# POWER.net
KiCad netlist of a schematic drawn in Altium Designer
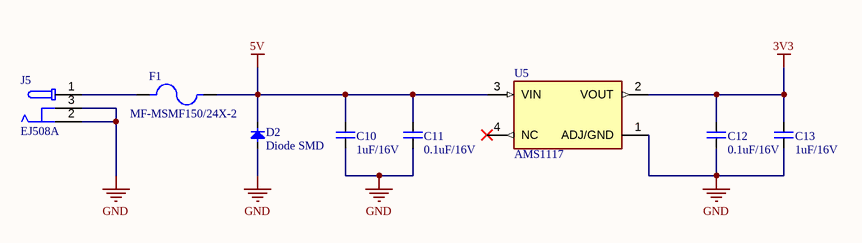
[diagram p0: POWER.SchDoc]

(export (version "E")
  (design (tool "Eeschema 10.0.6"))
  (components
    (comp (ref "C10")
      (value "1uF/16V")
      (footprint "CAP_C_1608X80")
      (description "CAP_Chip")
      (libsource (lib "BTL_SCHLIB") (part "CAP_SMD"))
    )
    (comp (ref "C11")
      (value "0.1uF/16V")
      (footprint "CAP_C_1608X80")
      (description "CAP_Chip")
      (libsource (lib "BTL_SCHLIB") (part "CAP_SMD"))
    )
    (comp (ref "C12")
      (value "0.1uF/16V")
      (footprint "CAP_C_1608X80")
      (description "CAP_Chip")
      (libsource (lib "BTL_SCHLIB") (part "CAP_SMD"))
    )
    (comp (ref "C13")
      (value "1uF/16V")
      (footprint "CAP_C_1608X80")
      (description "CAP_Chip")
      (libsource (lib "BTL_SCHLIB") (part "CAP_SMD"))
    )
    (comp (ref "D2")
      (value "Diode SMD")
      (footprint "DO-214AC_SMA")
      (description "Default Diode")
      (fields (field (name "PUBLISHER") "Altium Limited"))
      (libsource (lib "BTL_SCHLIB") (part "Diode SMD"))
    )
    (comp (ref "F1")
      (value "MF-MSMF150/24X-2")
      (footprint "FUSER_MF-MSMF150/24X-2")
      (description "Polymeric PTC Resettable Fuse 24V 1.5 A Ih Surface Mount 1812 (4532 Metric), Concave")
      (fields (field (name "DIGI-KEY_PART_NUMBER") "MF-MSMF150/24X-2TR-ND") (field (name "MF") "Bourns"))
      (libsource (lib "BTL_SCHLIB") (part "MF-MSMF150/24X-2"))
    )
    (comp (ref "J5")
      (value "EJ508A")
      (footprint "MPD_EJ508A")
      (description "Power Barrel Connector Jack 2.10mm ID _0.083_, 5.50mm OD _0.217_ Through Hole, Right Angle")
      (fields (field (name "MF") "MPD"))
      (libsource (lib "BTL_SCHLIB") (part "EJ508A"))
    )
    (comp (ref "U5")
      (value "AMS1117")
      (footprint "SOT229P700X180-4N")
      (description "1A LOW DROPOUT VOLTAGE REGULATOR SOT-223")
      (fields (field (name "MF") "Advanced Monolithic Systems"))
      (libsource (lib "BTL_SCHLIB") (part "AMS1117"))
    )
  )
  (nets
    (net (code "1") (name "3V3") (class "Default")
      (node (ref "C12") (pin "2") (pinfunction "2_2") (pintype "passive"))
      (node (ref "C13") (pin "2") (pinfunction "2_2") (pintype "passive"))
      (node (ref "U5") (pin "2") (pinfunction "VOUT_2") (pintype "output"))
    )
    (net (code "2") (name "5V") (class "Default")
      (node (ref "C10") (pin "2") (pinfunction "2_2") (pintype "passive"))
      (node (ref "C11") (pin "2") (pinfunction "2_2") (pintype "passive"))
      (node (ref "D2") (pin "1") (pinfunction "K_1") (pintype "passive"))
      (node (ref "F1") (pin "2") (pinfunction "2_2") (pintype "passive"))
      (node (ref "U5") (pin "3") (pinfunction "VIN_3") (pintype "input"))
    )
    (net (code "3") (name "GND") (class "Default")
      (node (ref "C10") (pin "1") (pinfunction "1_1") (pintype "passive"))
      (node (ref "C11") (pin "1") (pinfunction "1_1") (pintype "passive"))
      (node (ref "C12") (pin "1") (pinfunction "1_1") (pintype "passive"))
      (node (ref "C13") (pin "1") (pinfunction "1_1") (pintype "passive"))
      (node (ref "D2") (pin "2") (pinfunction "A_2") (pintype "passive"))
      (node (ref "J5") (pin "2") (pinfunction "2_2") (pintype "passive"))
      (node (ref "J5") (pin "3") (pinfunction "3_3") (pintype "passive"))
      (node (ref "U5") (pin "1") (pinfunction "ADJ/GND_1") (pintype "power_in"))
    )
    (net (code "4") (name "Net-(F1-Pad1)") (class "Default")
      (node (ref "F1") (pin "1") (pinfunction "1_1") (pintype "passive"))
      (node (ref "J5") (pin "1") (pinfunction "1_1") (pintype "passive"))
    )
    (net (code "5") (name "unconnected-(U5-NC-Pad4)") (class "Default")
      (node (ref "U5") (pin "4") (pinfunction "NC_4") (pintype "output+no_connect"))
    )
  )
)
